# 8x8-MotorState.net
KiCad netlist of a schematic drawn in EAGLE
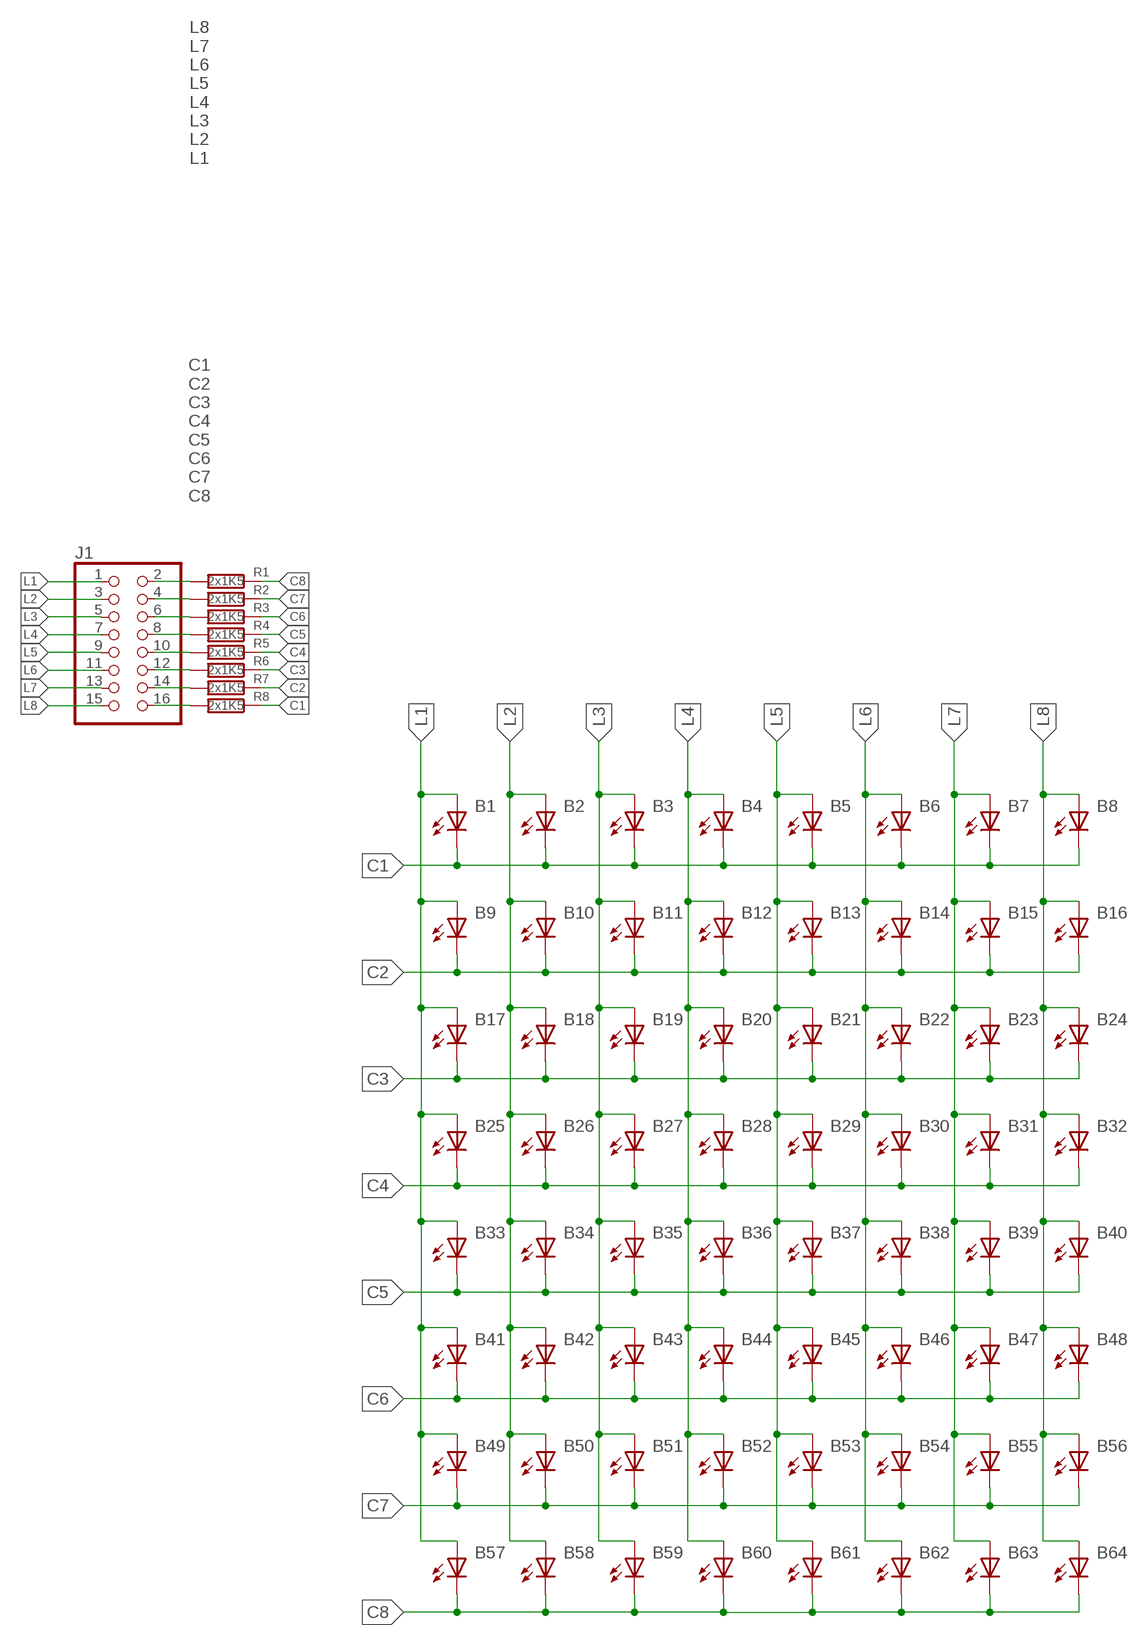
[diagram p0: schematic, sheet 1]

(export (version "E")
  (design (tool "Eeschema 10.0.6"))
  (components
    (comp (ref "B1")
      (value "LED2835")
      (footprint "eagle-import:LED2835")
      (libsource (lib "eagle-import") (part "LED2835"))
    )
    (comp (ref "B2")
      (value "LED2835")
      (footprint "eagle-import:LED2835")
      (libsource (lib "eagle-import") (part "LED2835"))
    )
    (comp (ref "B3")
      (value "LED2835")
      (footprint "eagle-import:LED2835")
      (libsource (lib "eagle-import") (part "LED2835"))
    )
    (comp (ref "B4")
      (value "LED2835")
      (footprint "eagle-import:LED2835")
      (libsource (lib "eagle-import") (part "LED2835"))
    )
    (comp (ref "B5")
      (value "LED2835")
      (footprint "eagle-import:LED2835")
      (libsource (lib "eagle-import") (part "LED2835"))
    )
    (comp (ref "B6")
      (value "LED2835")
      (footprint "eagle-import:LED2835")
      (libsource (lib "eagle-import") (part "LED2835"))
    )
    (comp (ref "B7")
      (value "LED2835")
      (footprint "eagle-import:LED2835")
      (libsource (lib "eagle-import") (part "LED2835"))
    )
    (comp (ref "B8")
      (value "LED2835")
      (footprint "eagle-import:LED2835")
      (libsource (lib "eagle-import") (part "LED2835"))
    )
    (comp (ref "B9")
      (value "LED2835")
      (footprint "eagle-import:LED2835")
      (libsource (lib "eagle-import") (part "LED2835"))
    )
    (comp (ref "B10")
      (value "LED2835")
      (footprint "eagle-import:LED2835")
      (libsource (lib "eagle-import") (part "LED2835"))
    )
    (comp (ref "B11")
      (value "LED2835")
      (footprint "eagle-import:LED2835")
      (libsource (lib "eagle-import") (part "LED2835"))
    )
    (comp (ref "B12")
      (value "LED2835")
      (footprint "eagle-import:LED2835")
      (libsource (lib "eagle-import") (part "LED2835"))
    )
    (comp (ref "B13")
      (value "LED2835")
      (footprint "eagle-import:LED2835")
      (libsource (lib "eagle-import") (part "LED2835"))
    )
    (comp (ref "B14")
      (value "LED2835")
      (footprint "eagle-import:LED2835")
      (libsource (lib "eagle-import") (part "LED2835"))
    )
    (comp (ref "B15")
      (value "LED2835")
      (footprint "eagle-import:LED2835")
      (libsource (lib "eagle-import") (part "LED2835"))
    )
    (comp (ref "B16")
      (value "LED2835")
      (footprint "eagle-import:LED2835")
      (libsource (lib "eagle-import") (part "LED2835"))
    )
    (comp (ref "B17")
      (value "LED2835")
      (footprint "eagle-import:LED2835")
      (libsource (lib "eagle-import") (part "LED2835"))
    )
    (comp (ref "B18")
      (value "LED2835")
      (footprint "eagle-import:LED2835")
      (libsource (lib "eagle-import") (part "LED2835"))
    )
    (comp (ref "B19")
      (value "LED2835")
      (footprint "eagle-import:LED2835")
      (libsource (lib "eagle-import") (part "LED2835"))
    )
    (comp (ref "B20")
      (value "LED2835")
      (footprint "eagle-import:LED2835")
      (libsource (lib "eagle-import") (part "LED2835"))
    )
    (comp (ref "B21")
      (value "LED2835")
      (footprint "eagle-import:LED2835")
      (libsource (lib "eagle-import") (part "LED2835"))
    )
    (comp (ref "B22")
      (value "LED2835")
      (footprint "eagle-import:LED2835")
      (libsource (lib "eagle-import") (part "LED2835"))
    )
    (comp (ref "B23")
      (value "LED2835")
      (footprint "eagle-import:LED2835")
      (libsource (lib "eagle-import") (part "LED2835"))
    )
    (comp (ref "B24")
      (value "LED2835")
      (footprint "eagle-import:LED2835")
      (libsource (lib "eagle-import") (part "LED2835"))
    )
    (comp (ref "B25")
      (value "LED2835")
      (footprint "eagle-import:LED2835")
      (libsource (lib "eagle-import") (part "LED2835"))
    )
    (comp (ref "B26")
      (value "LED2835")
      (footprint "eagle-import:LED2835")
      (libsource (lib "eagle-import") (part "LED2835"))
    )
    (comp (ref "B27")
      (value "LED2835")
      (footprint "eagle-import:LED2835")
      (libsource (lib "eagle-import") (part "LED2835"))
    )
    (comp (ref "B28")
      (value "LED2835")
      (footprint "eagle-import:LED2835")
      (libsource (lib "eagle-import") (part "LED2835"))
    )
    (comp (ref "B29")
      (value "LED2835")
      (footprint "eagle-import:LED2835")
      (libsource (lib "eagle-import") (part "LED2835"))
    )
    (comp (ref "B30")
      (value "LED2835")
      (footprint "eagle-import:LED2835")
      (libsource (lib "eagle-import") (part "LED2835"))
    )
    (comp (ref "B31")
      (value "LED2835")
      (footprint "eagle-import:LED2835")
      (libsource (lib "eagle-import") (part "LED2835"))
    )
    (comp (ref "B32")
      (value "LED2835")
      (footprint "eagle-import:LED2835")
      (libsource (lib "eagle-import") (part "LED2835"))
    )
    (comp (ref "B33")
      (value "LED2835")
      (footprint "eagle-import:LED2835")
      (libsource (lib "eagle-import") (part "LED2835"))
    )
    (comp (ref "B34")
      (value "LED2835")
      (footprint "eagle-import:LED2835")
      (libsource (lib "eagle-import") (part "LED2835"))
    )
    (comp (ref "B35")
      (value "LED2835")
      (footprint "eagle-import:LED2835")
      (libsource (lib "eagle-import") (part "LED2835"))
    )
    (comp (ref "B36")
      (value "LED2835")
      (footprint "eagle-import:LED2835")
      (libsource (lib "eagle-import") (part "LED2835"))
    )
    (comp (ref "B37")
      (value "LED2835")
      (footprint "eagle-import:LED2835")
      (libsource (lib "eagle-import") (part "LED2835"))
    )
    (comp (ref "B38")
      (value "LED2835")
      (footprint "eagle-import:LED2835")
      (libsource (lib "eagle-import") (part "LED2835"))
    )
    (comp (ref "B39")
      (value "LED2835")
      (footprint "eagle-import:LED2835")
      (libsource (lib "eagle-import") (part "LED2835"))
    )
    (comp (ref "B40")
      (value "LED2835")
      (footprint "eagle-import:LED2835")
      (libsource (lib "eagle-import") (part "LED2835"))
    )
    (comp (ref "B41")
      (value "LED2835")
      (footprint "eagle-import:LED2835")
      (libsource (lib "eagle-import") (part "LED2835"))
    )
    (comp (ref "B42")
      (value "LED2835")
      (footprint "eagle-import:LED2835")
      (libsource (lib "eagle-import") (part "LED2835"))
    )
    (comp (ref "B43")
      (value "LED2835")
      (footprint "eagle-import:LED2835")
      (libsource (lib "eagle-import") (part "LED2835"))
    )
    (comp (ref "B44")
      (value "LED2835")
      (footprint "eagle-import:LED2835")
      (libsource (lib "eagle-import") (part "LED2835"))
    )
    (comp (ref "B45")
      (value "LED2835")
      (footprint "eagle-import:LED2835")
      (libsource (lib "eagle-import") (part "LED2835"))
    )
    (comp (ref "B46")
      (value "LED2835")
      (footprint "eagle-import:LED2835")
      (libsource (lib "eagle-import") (part "LED2835"))
    )
    (comp (ref "B47")
      (value "LED2835")
      (footprint "eagle-import:LED2835")
      (libsource (lib "eagle-import") (part "LED2835"))
    )
    (comp (ref "B48")
      (value "LED2835")
      (footprint "eagle-import:LED2835")
      (libsource (lib "eagle-import") (part "LED2835"))
    )
    (comp (ref "B49")
      (value "LED2835")
      (footprint "eagle-import:LED2835")
      (libsource (lib "eagle-import") (part "LED2835"))
    )
    (comp (ref "B50")
      (value "LED2835")
      (footprint "eagle-import:LED2835")
      (libsource (lib "eagle-import") (part "LED2835"))
    )
    (comp (ref "B51")
      (value "LED2835")
      (footprint "eagle-import:LED2835")
      (libsource (lib "eagle-import") (part "LED2835"))
    )
    (comp (ref "B52")
      (value "LED2835")
      (footprint "eagle-import:LED2835")
      (libsource (lib "eagle-import") (part "LED2835"))
    )
    (comp (ref "B53")
      (value "LED2835")
      (footprint "eagle-import:LED2835")
      (libsource (lib "eagle-import") (part "LED2835"))
    )
    (comp (ref "B54")
      (value "LED2835")
      (footprint "eagle-import:LED2835")
      (libsource (lib "eagle-import") (part "LED2835"))
    )
    (comp (ref "B55")
      (value "LED2835")
      (footprint "eagle-import:LED2835")
      (libsource (lib "eagle-import") (part "LED2835"))
    )
    (comp (ref "B56")
      (value "LED2835")
      (footprint "eagle-import:LED2835")
      (libsource (lib "eagle-import") (part "LED2835"))
    )
    (comp (ref "B57")
      (value "LED2835")
      (footprint "eagle-import:LED2835")
      (libsource (lib "eagle-import") (part "LED2835"))
    )
    (comp (ref "B58")
      (value "LED2835")
      (footprint "eagle-import:LED2835")
      (libsource (lib "eagle-import") (part "LED2835"))
    )
    (comp (ref "B59")
      (value "LED2835")
      (footprint "eagle-import:LED2835")
      (libsource (lib "eagle-import") (part "LED2835"))
    )
    (comp (ref "B60")
      (value "LED2835")
      (footprint "eagle-import:LED2835")
      (libsource (lib "eagle-import") (part "LED2835"))
    )
    (comp (ref "B61")
      (value "LED2835")
      (footprint "eagle-import:LED2835")
      (libsource (lib "eagle-import") (part "LED2835"))
    )
    (comp (ref "B62")
      (value "LED2835")
      (footprint "eagle-import:LED2835")
      (libsource (lib "eagle-import") (part "LED2835"))
    )
    (comp (ref "B63")
      (value "LED2835")
      (footprint "eagle-import:LED2835")
      (libsource (lib "eagle-import") (part "LED2835"))
    )
    (comp (ref "B64")
      (value "LED2835")
      (footprint "eagle-import:LED2835")
      (libsource (lib "eagle-import") (part "LED2835"))
    )
    (comp (ref "J1")
      (value "PINHEAD_2X8PTH")
      (footprint "eagle-import:PINHEAD-2X08")
      (libsource (lib "eagle-import") (part "PINHEAD_2X8PTH"))
    )
    (comp (ref "R1")
      (value "2x1K5")
      (footprint "eagle-import:R1206")
      (libsource (lib "eagle-import") (part "RESISTOR_1206"))
    )
    (comp (ref "R2")
      (value "2x1K5")
      (footprint "eagle-import:R1206")
      (libsource (lib "eagle-import") (part "RESISTOR_1206"))
    )
    (comp (ref "R3")
      (value "2x1K5")
      (footprint "eagle-import:R1206")
      (libsource (lib "eagle-import") (part "RESISTOR_1206"))
    )
    (comp (ref "R4")
      (value "2x1K5")
      (footprint "eagle-import:R1206")
      (libsource (lib "eagle-import") (part "RESISTOR_1206"))
    )
    (comp (ref "R5")
      (value "2x1K5")
      (footprint "eagle-import:R1206")
      (libsource (lib "eagle-import") (part "RESISTOR_1206"))
    )
    (comp (ref "R6")
      (value "2x1K5")
      (footprint "eagle-import:R1206")
      (libsource (lib "eagle-import") (part "RESISTOR_1206"))
    )
    (comp (ref "R7")
      (value "2x1K5")
      (footprint "eagle-import:R1206")
      (libsource (lib "eagle-import") (part "RESISTOR_1206"))
    )
    (comp (ref "R8")
      (value "2x1K5")
      (footprint "eagle-import:R1206")
      (libsource (lib "eagle-import") (part "RESISTOR_1206"))
    )
  )
  (nets
    (net (code "1") (name "C1") (class "Default")
      (node (ref "B1") (pin "C") (pinfunction "C_C") (pintype "passive"))
      (node (ref "B2") (pin "C") (pinfunction "C_C") (pintype "passive"))
      (node (ref "B3") (pin "C") (pinfunction "C_C") (pintype "passive"))
      (node (ref "B4") (pin "C") (pinfunction "C_C") (pintype "passive"))
      (node (ref "B5") (pin "C") (pinfunction "C_C") (pintype "passive"))
      (node (ref "B6") (pin "C") (pinfunction "C_C") (pintype "passive"))
      (node (ref "B7") (pin "C") (pinfunction "C_C") (pintype "passive"))
      (node (ref "B8") (pin "C") (pinfunction "C_C") (pintype "passive"))
      (node (ref "R8") (pin "1") (pinfunction "1_1") (pintype "passive"))
    )
    (net (code "2") (name "C2") (class "Default")
      (node (ref "B10") (pin "C") (pinfunction "C_C") (pintype "passive"))
      (node (ref "B11") (pin "C") (pinfunction "C_C") (pintype "passive"))
      (node (ref "B12") (pin "C") (pinfunction "C_C") (pintype "passive"))
      (node (ref "B13") (pin "C") (pinfunction "C_C") (pintype "passive"))
      (node (ref "B14") (pin "C") (pinfunction "C_C") (pintype "passive"))
      (node (ref "B15") (pin "C") (pinfunction "C_C") (pintype "passive"))
      (node (ref "B16") (pin "C") (pinfunction "C_C") (pintype "passive"))
      (node (ref "B9") (pin "C") (pinfunction "C_C") (pintype "passive"))
      (node (ref "R7") (pin "1") (pinfunction "1_1") (pintype "passive"))
    )
    (net (code "3") (name "C3") (class "Default")
      (node (ref "B17") (pin "C") (pinfunction "C_C") (pintype "passive"))
      (node (ref "B18") (pin "C") (pinfunction "C_C") (pintype "passive"))
      (node (ref "B19") (pin "C") (pinfunction "C_C") (pintype "passive"))
      (node (ref "B20") (pin "C") (pinfunction "C_C") (pintype "passive"))
      (node (ref "B21") (pin "C") (pinfunction "C_C") (pintype "passive"))
      (node (ref "B22") (pin "C") (pinfunction "C_C") (pintype "passive"))
      (node (ref "B23") (pin "C") (pinfunction "C_C") (pintype "passive"))
      (node (ref "B24") (pin "C") (pinfunction "C_C") (pintype "passive"))
      (node (ref "R6") (pin "1") (pinfunction "1_1") (pintype "passive"))
    )
    (net (code "4") (name "C4") (class "Default")
      (node (ref "B25") (pin "C") (pinfunction "C_C") (pintype "passive"))
      (node (ref "B26") (pin "C") (pinfunction "C_C") (pintype "passive"))
      (node (ref "B27") (pin "C") (pinfunction "C_C") (pintype "passive"))
      (node (ref "B28") (pin "C") (pinfunction "C_C") (pintype "passive"))
      (node (ref "B29") (pin "C") (pinfunction "C_C") (pintype "passive"))
      (node (ref "B30") (pin "C") (pinfunction "C_C") (pintype "passive"))
      (node (ref "B31") (pin "C") (pinfunction "C_C") (pintype "passive"))
      (node (ref "B32") (pin "C") (pinfunction "C_C") (pintype "passive"))
      (node (ref "R5") (pin "1") (pinfunction "1_1") (pintype "passive"))
    )
    (net (code "5") (name "C5") (class "Default")
      (node (ref "B33") (pin "C") (pinfunction "C_C") (pintype "passive"))
      (node (ref "B34") (pin "C") (pinfunction "C_C") (pintype "passive"))
      (node (ref "B35") (pin "C") (pinfunction "C_C") (pintype "passive"))
      (node (ref "B36") (pin "C") (pinfunction "C_C") (pintype "passive"))
      (node (ref "B37") (pin "C") (pinfunction "C_C") (pintype "passive"))
      (node (ref "B38") (pin "C") (pinfunction "C_C") (pintype "passive"))
      (node (ref "B39") (pin "C") (pinfunction "C_C") (pintype "passive"))
      (node (ref "B40") (pin "C") (pinfunction "C_C") (pintype "passive"))
      (node (ref "R4") (pin "1") (pinfunction "1_1") (pintype "passive"))
    )
    (net (code "6") (name "C6") (class "Default")
      (node (ref "B41") (pin "C") (pinfunction "C_C") (pintype "passive"))
      (node (ref "B42") (pin "C") (pinfunction "C_C") (pintype "passive"))
      (node (ref "B43") (pin "C") (pinfunction "C_C") (pintype "passive"))
      (node (ref "B44") (pin "C") (pinfunction "C_C") (pintype "passive"))
      (node (ref "B45") (pin "C") (pinfunction "C_C") (pintype "passive"))
      (node (ref "B46") (pin "C") (pinfunction "C_C") (pintype "passive"))
      (node (ref "B47") (pin "C") (pinfunction "C_C") (pintype "passive"))
      (node (ref "B48") (pin "C") (pinfunction "C_C") (pintype "passive"))
      (node (ref "R3") (pin "1") (pinfunction "1_1") (pintype "passive"))
    )
    (net (code "7") (name "C7") (class "Default")
      (node (ref "B49") (pin "C") (pinfunction "C_C") (pintype "passive"))
      (node (ref "B50") (pin "C") (pinfunction "C_C") (pintype "passive"))
      (node (ref "B51") (pin "C") (pinfunction "C_C") (pintype "passive"))
      (node (ref "B52") (pin "C") (pinfunction "C_C") (pintype "passive"))
      (node (ref "B53") (pin "C") (pinfunction "C_C") (pintype "passive"))
      (node (ref "B54") (pin "C") (pinfunction "C_C") (pintype "passive"))
      (node (ref "B55") (pin "C") (pinfunction "C_C") (pintype "passive"))
      (node (ref "B56") (pin "C") (pinfunction "C_C") (pintype "passive"))
      (node (ref "R2") (pin "1") (pinfunction "1_1") (pintype "passive"))
    )
    (net (code "8") (name "C8") (class "Default")
      (node (ref "B57") (pin "C") (pinfunction "C_C") (pintype "passive"))
      (node (ref "B58") (pin "C") (pinfunction "C_C") (pintype "passive"))
      (node (ref "B59") (pin "C") (pinfunction "C_C") (pintype "passive"))
      (node (ref "B60") (pin "C") (pinfunction "C_C") (pintype "passive"))
      (node (ref "B61") (pin "C") (pinfunction "C_C") (pintype "passive"))
      (node (ref "B62") (pin "C") (pinfunction "C_C") (pintype "passive"))
      (node (ref "B63") (pin "C") (pinfunction "C_C") (pintype "passive"))
      (node (ref "B64") (pin "C") (pinfunction "C_C") (pintype "passive"))
      (node (ref "R1") (pin "1") (pinfunction "1_1") (pintype "passive"))
    )
    (net (code "9") (name "L1") (class "Default")
      (node (ref "B1") (pin "A") (pinfunction "A_A") (pintype "passive"))
      (node (ref "B17") (pin "A") (pinfunction "A_A") (pintype "passive"))
      (node (ref "B25") (pin "A") (pinfunction "A_A") (pintype "passive"))
      (node (ref "B33") (pin "A") (pinfunction "A_A") (pintype "passive"))
      (node (ref "B41") (pin "A") (pinfunction "A_A") (pintype "passive"))
      (node (ref "B49") (pin "A") (pinfunction "A_A") (pintype "passive"))
      (node (ref "B57") (pin "A") (pinfunction "A_A") (pintype "passive"))
      (node (ref "B9") (pin "A") (pinfunction "A_A") (pintype "passive"))
      (node (ref "J1") (pin "1") (pinfunction "1_1") (pintype "passive"))
    )
    (net (code "10") (name "L2") (class "Default")
      (node (ref "B10") (pin "A") (pinfunction "A_A") (pintype "passive"))
      (node (ref "B18") (pin "A") (pinfunction "A_A") (pintype "passive"))
      (node (ref "B2") (pin "A") (pinfunction "A_A") (pintype "passive"))
      (node (ref "B26") (pin "A") (pinfunction "A_A") (pintype "passive"))
      (node (ref "B34") (pin "A") (pinfunction "A_A") (pintype "passive"))
      (node (ref "B42") (pin "A") (pinfunction "A_A") (pintype "passive"))
      (node (ref "B50") (pin "A") (pinfunction "A_A") (pintype "passive"))
      (node (ref "B58") (pin "A") (pinfunction "A_A") (pintype "passive"))
      (node (ref "J1") (pin "3") (pinfunction "3_3") (pintype "passive"))
    )
    (net (code "11") (name "L3") (class "Default")
      (node (ref "B11") (pin "A") (pinfunction "A_A") (pintype "passive"))
      (node (ref "B19") (pin "A") (pinfunction "A_A") (pintype "passive"))
      (node (ref "B27") (pin "A") (pinfunction "A_A") (pintype "passive"))
      (node (ref "B3") (pin "A") (pinfunction "A_A") (pintype "passive"))
      (node (ref "B35") (pin "A") (pinfunction "A_A") (pintype "passive"))
      (node (ref "B43") (pin "A") (pinfunction "A_A") (pintype "passive"))
      (node (ref "B51") (pin "A") (pinfunction "A_A") (pintype "passive"))
      (node (ref "B59") (pin "A") (pinfunction "A_A") (pintype "passive"))
      (node (ref "J1") (pin "5") (pinfunction "5_5") (pintype "passive"))
    )
    (net (code "12") (name "L4") (class "Default")
      (node (ref "B12") (pin "A") (pinfunction "A_A") (pintype "passive"))
      (node (ref "B20") (pin "A") (pinfunction "A_A") (pintype "passive"))
      (node (ref "B28") (pin "A") (pinfunction "A_A") (pintype "passive"))
      (node (ref "B36") (pin "A") (pinfunction "A_A") (pintype "passive"))
      (node (ref "B4") (pin "A") (pinfunction "A_A") (pintype "passive"))
      (node (ref "B44") (pin "A") (pinfunction "A_A") (pintype "passive"))
      (node (ref "B52") (pin "A") (pinfunction "A_A") (pintype "passive"))
      (node (ref "B60") (pin "A") (pinfunction "A_A") (pintype "passive"))
      (node (ref "J1") (pin "7") (pinfunction "7_7") (pintype "passive"))
    )
    (net (code "13") (name "L5") (class "Default")
      (node (ref "B13") (pin "A") (pinfunction "A_A") (pintype "passive"))
      (node (ref "B21") (pin "A") (pinfunction "A_A") (pintype "passive"))
      (node (ref "B29") (pin "A") (pinfunction "A_A") (pintype "passive"))
      (node (ref "B37") (pin "A") (pinfunction "A_A") (pintype "passive"))
      (node (ref "B45") (pin "A") (pinfunction "A_A") (pintype "passive"))
      (node (ref "B5") (pin "A") (pinfunction "A_A") (pintype "passive"))
      (node (ref "B53") (pin "A") (pinfunction "A_A") (pintype "passive"))
      (node (ref "B61") (pin "A") (pinfunction "A_A") (pintype "passive"))
      (node (ref "J1") (pin "9") (pinfunction "9_9") (pintype "passive"))
    )
    (net (code "14") (name "L6") (class "Default")
      (node (ref "B14") (pin "A") (pinfunction "A_A") (pintype "passive"))
      (node (ref "B22") (pin "A") (pinfunction "A_A") (pintype "passive"))
      (node (ref "B30") (pin "A") (pinfunction "A_A") (pintype "passive"))
      (node (ref "B38") (pin "A") (pinfunction "A_A") (pintype "passive"))
      (node (ref "B46") (pin "A") (pinfunction "A_A") (pintype "passive"))
      (node (ref "B54") (pin "A") (pinfunction "A_A") (pintype "passive"))
      (node (ref "B6") (pin "A") (pinfunction "A_A") (pintype "passive"))
      (node (ref "B62") (pin "A") (pinfunction "A_A") (pintype "passive"))
      (node (ref "J1") (pin "11") (pinfunction "11_11") (pintype "passive"))
    )
    (net (code "15") (name "L7") (class "Default")
      (node (ref "B15") (pin "A") (pinfunction "A_A") (pintype "passive"))
      (node (ref "B23") (pin "A") (pinfunction "A_A") (pintype "passive"))
      (node (ref "B31") (pin "A") (pinfunction "A_A") (pintype "passive"))
      (node (ref "B39") (pin "A") (pinfunction "A_A") (pintype "passive"))
      (node (ref "B47") (pin "A") (pinfunction "A_A") (pintype "passive"))
      (node (ref "B55") (pin "A") (pinfunction "A_A") (pintype "passive"))
      (node (ref "B63") (pin "A") (pinfunction "A_A") (pintype "passive"))
      (node (ref "B7") (pin "A") (pinfunction "A_A") (pintype "passive"))
      (node (ref "J1") (pin "13") (pinfunction "13_13") (pintype "passive"))
    )
    (net (code "16") (name "L8") (class "Default")
      (node (ref "B16") (pin "A") (pinfunction "A_A") (pintype "passive"))
      (node (ref "B24") (pin "A") (pinfunction "A_A") (pintype "passive"))
      (node (ref "B32") (pin "A") (pinfunction "A_A") (pintype "passive"))
      (node (ref "B40") (pin "A") (pinfunction "A_A") (pintype "passive"))
      (node (ref "B48") (pin "A") (pinfunction "A_A") (pintype "passive"))
      (node (ref "B56") (pin "A") (pinfunction "A_A") (pintype "passive"))
      (node (ref "B64") (pin "A") (pinfunction "A_A") (pintype "passive"))
      (node (ref "B8") (pin "A") (pinfunction "A_A") (pintype "passive"))
      (node (ref "J1") (pin "15") (pinfunction "15_15") (pintype "passive"))
    )
    (net (code "17") (name "Net-(J1-Pad2)") (class "Default")
      (node (ref "J1") (pin "2") (pinfunction "2_2") (pintype "passive"))
      (node (ref "R1") (pin "2") (pinfunction "2_2") (pintype "passive"))
    )
    (net (code "18") (name "Net-(J1-Pad4)") (class "Default")
      (node (ref "J1") (pin "4") (pinfunction "4_4") (pintype "passive"))
      (node (ref "R2") (pin "2") (pinfunction "2_2") (pintype "passive"))
    )
    (net (code "19") (name "Net-(J1-Pad6)") (class "Default")
      (node (ref "J1") (pin "6") (pinfunction "6_6") (pintype "passive"))
      (node (ref "R3") (pin "2") (pinfunction "2_2") (pintype "passive"))
    )
    (net (code "20") (name "Net-(J1-Pad8)") (class "Default")
      (node (ref "J1") (pin "8") (pinfunction "8_8") (pintype "passive"))
      (node (ref "R4") (pin "2") (pinfunction "2_2") (pintype "passive"))
    )
    (net (code "21") (name "Net-(J1-Pad10)") (class "Default")
      (node (ref "J1") (pin "10") (pinfunction "10_10") (pintype "passive"))
      (node (ref "R5") (pin "2") (pinfunction "2_2") (pintype "passive"))
    )
    (net (code "22") (name "Net-(J1-Pad12)") (class "Default")
      (node (ref "J1") (pin "12") (pinfunction "12_12") (pintype "passive"))
      (node (ref "R6") (pin "2") (pinfunction "2_2") (pintype "passive"))
    )
    (net (code "23") (name "Net-(J1-Pad14)") (class "Default")
      (node (ref "J1") (pin "14") (pinfunction "14_14") (pintype "passive"))
      (node (ref "R7") (pin "2") (pinfunction "2_2") (pintype "passive"))
    )
    (net (code "24") (name "Net-(J1-Pad16)") (class "Default")
      (node (ref "J1") (pin "16") (pinfunction "16_16") (pintype "passive"))
      (node (ref "R8") (pin "2") (pinfunction "2_2") (pintype "passive"))
    )
  )
)
